# SCH_New-Project_2024-06-23.net
KiCad netlist of a schematic drawn in EasyEDA
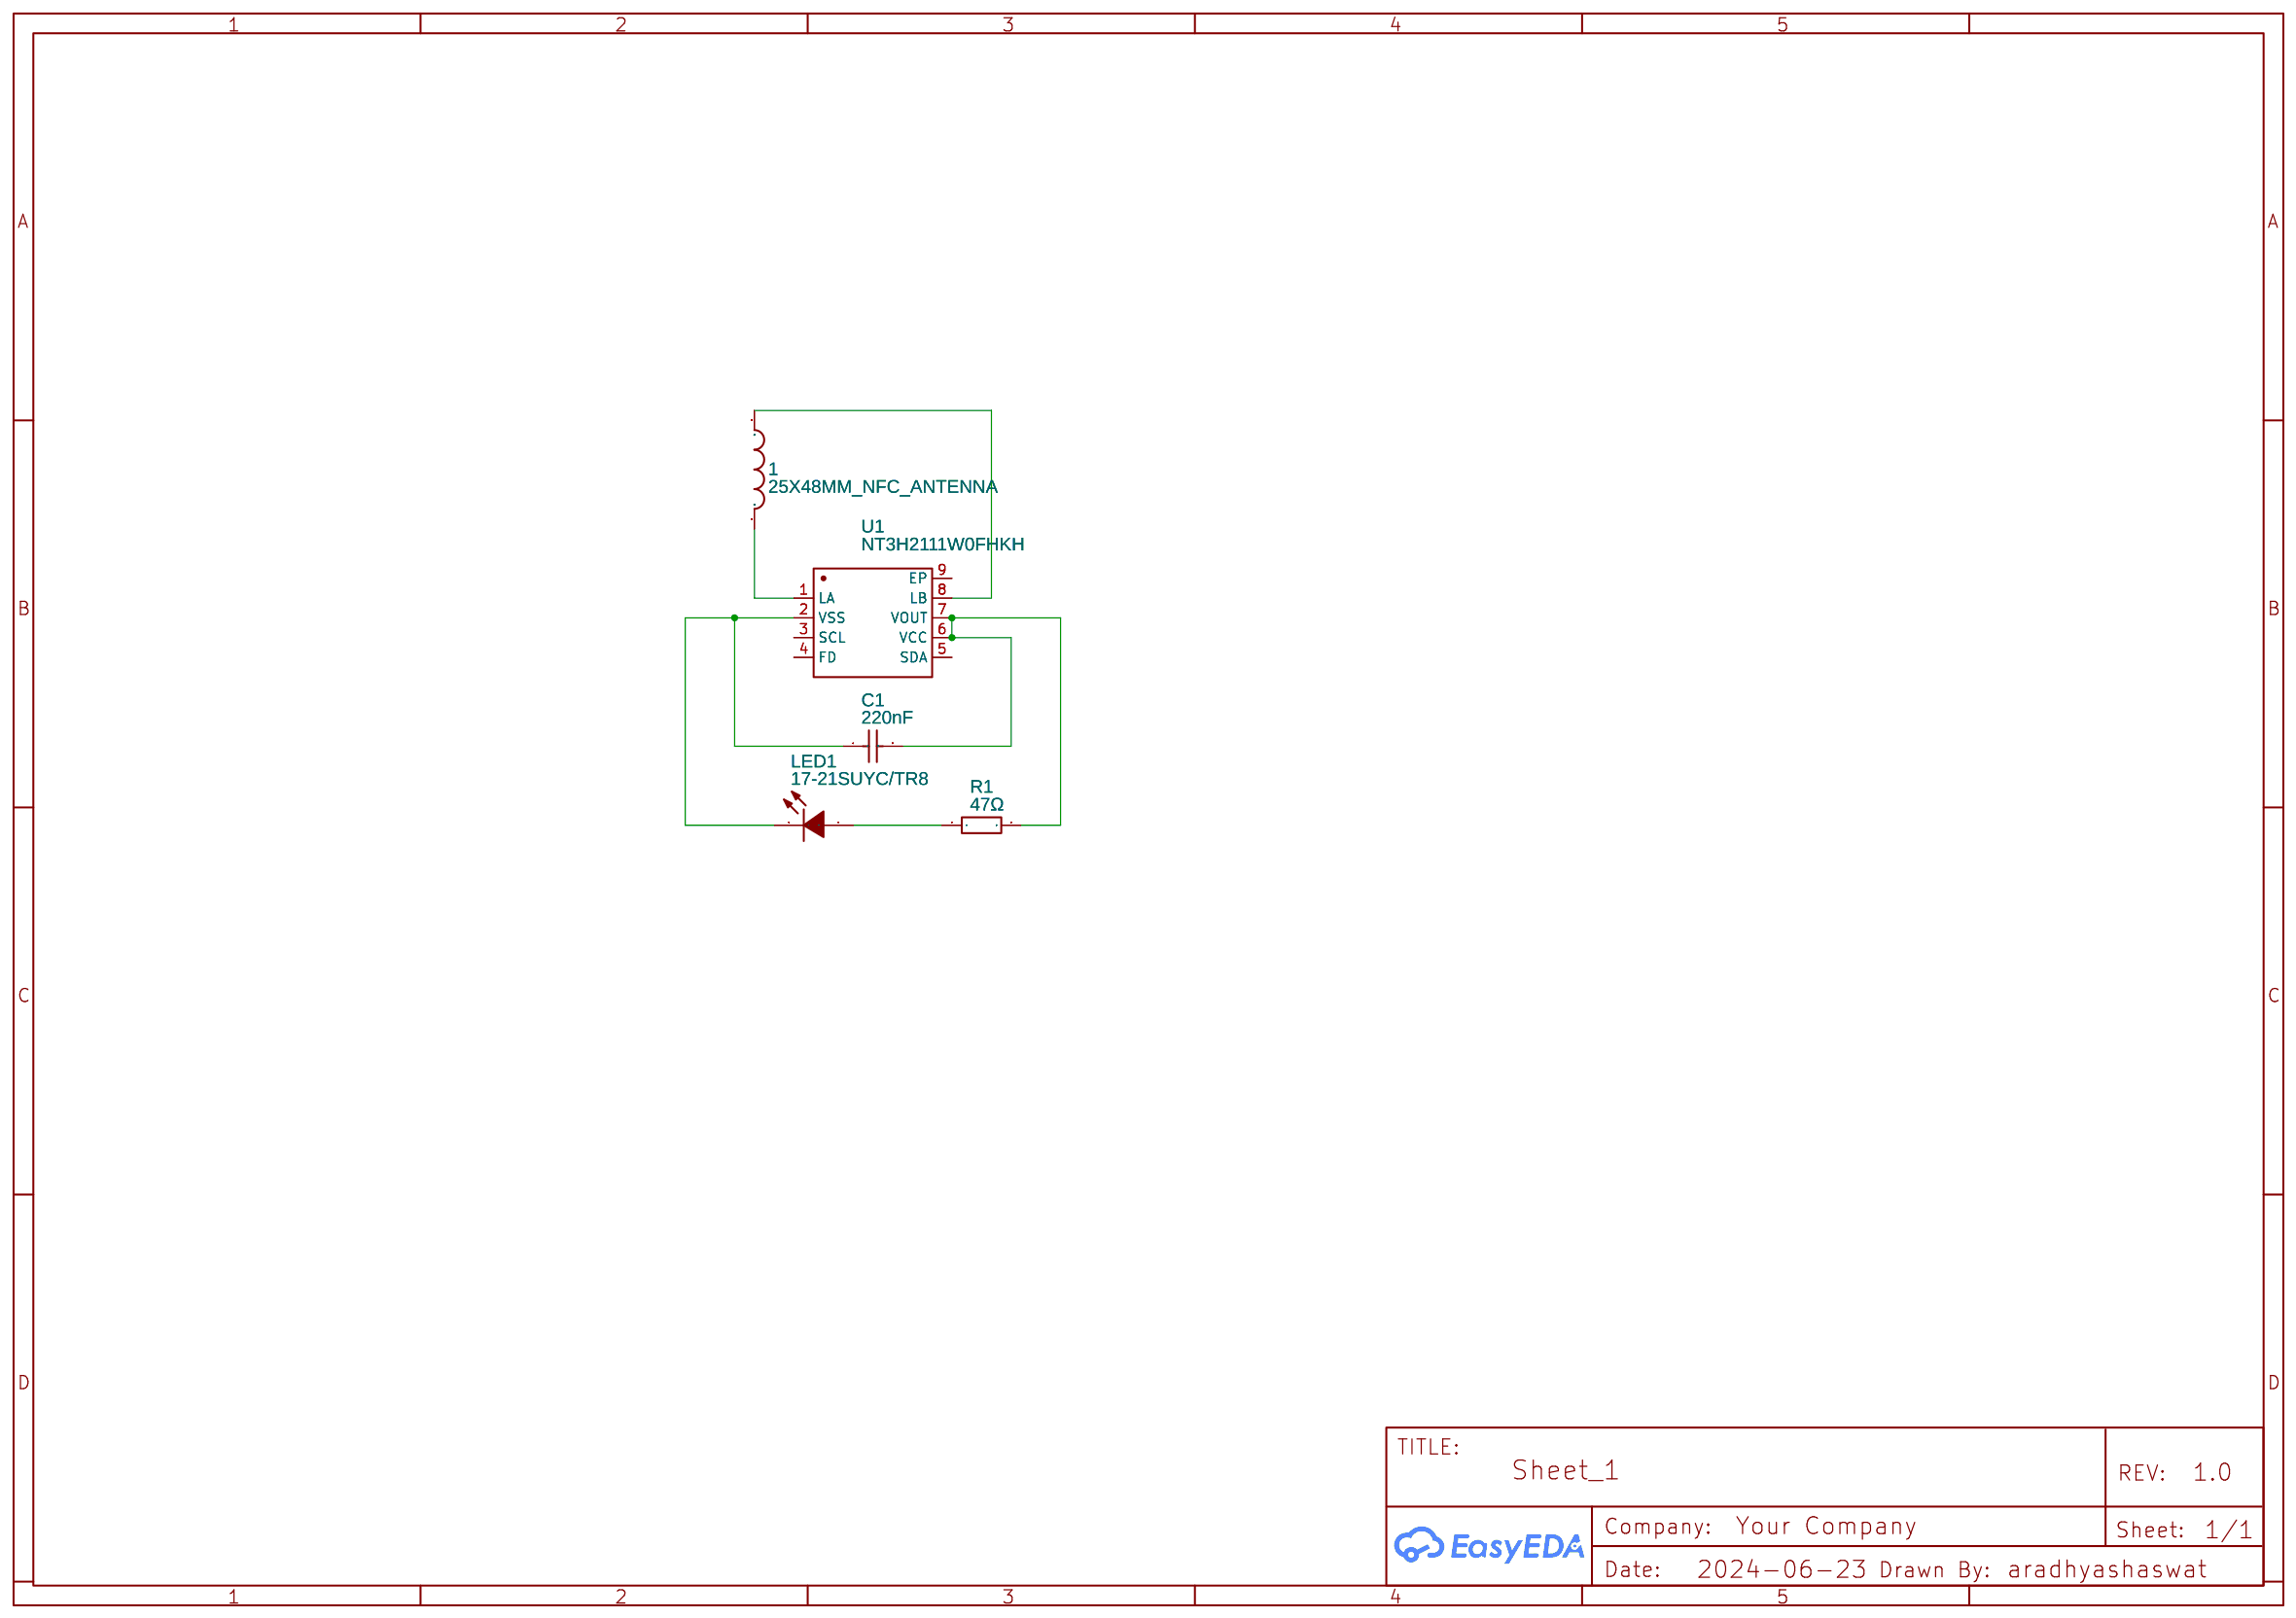
[diagram p0: schematic sheet]

(export (version "E")
  (design (tool "Eeschema 10.0.6"))
  (components
    (comp (ref "1") (value "25X48MM_NFC_ANTENNA") (libsource (lib "") (part "25X48MM_NFC_ANTENNA")))
    (comp (ref "C1")
      (value "220nF")
      (fields
        (field (name "Manufacturer Part") "CL10B224KA8NNNC")
        (field (name "Manufacturer") "SAMSUNG(三星)")
      )
      (libsource (lib "") (part "CL10B224KA8NNNC"))
    )
    (comp (ref "LED1")
      (value "17-21SUYC/TR8")
      (fields (field (name "Manufacturer Part") "KT-0805黄灯") (field (name "Manufacturer") "KENTO"))
      (libsource (lib "") (part "17-21SUYC/TR8"))
    )
    (comp (ref "R1")
      (value "47Ω")
      (fields
        (field (name "Manufacturer Part") "0603WAF470JT5E")
        (field (name "Manufacturer") "UNI-ROYAL(厚声)")
      )
      (libsource (lib "") (part "0603WAF470JT5E"))
    )
    (comp (ref "U1")
      (value "NT3H2111W0FHKH")
      (fields (field (name "Manufacturer") "NXP(恩智浦)"))
      (libsource (lib "") (part "NT3H2111W0FHKH"))
    )
  )
  (nets
    (net (code "1") (name "Net-(LED1-+)") (class "Default")
      (node (ref "LED1") (pin "1") (pinfunction "+_1") (pintype "unspecified"))
      (node (ref "R1") (pin "1") (pinfunction "1_1") (pintype "input"))
    )
    (net (code "2") (name "Net-(LED1--)") (class "Default")
      (node (ref "C1") (pin "1") (pinfunction "1_1") (pintype "input"))
      (node (ref "LED1") (pin "2") (pinfunction "-_2") (pintype "unspecified"))
      (node (ref "U1") (pin "2") (pinfunction "VSS_2") (pintype "unspecified"))
    )
    (net (code "3") (name "Net-(U1-LA)") (class "Default")
      (node (ref "1") (pin "P$2") (pinfunction "P$2_P$2") (pintype "bidirectional"))
      (node (ref "U1") (pin "1") (pinfunction "LA_1") (pintype "unspecified"))
    )
    (net (code "4") (name "Net-(U1-LB)") (class "Default")
      (node (ref "1") (pin "P$1") (pinfunction "P$1_P$1") (pintype "bidirectional"))
      (node (ref "U1") (pin "8") (pinfunction "LB_8") (pintype "unspecified"))
    )
    (net (code "5") (name "Net-(U1-VCC)") (class "Default")
      (node (ref "C1") (pin "2") (pinfunction "2_2") (pintype "input"))
      (node (ref "R1") (pin "2") (pinfunction "2_2") (pintype "input"))
      (node (ref "U1") (pin "6") (pinfunction "VCC_6") (pintype "unspecified"))
      (node (ref "U1") (pin "7") (pinfunction "VOUT_7") (pintype "unspecified"))
    )
    (net (code "6") (name "unconnected-(U1-EP-Pad9)") (class "Default")
      (node (ref "U1") (pin "9") (pinfunction "EP_9") (pintype "unspecified"))
    )
    (net (code "7") (name "unconnected-(U1-FD-Pad4)") (class "Default")
      (node (ref "U1") (pin "4") (pinfunction "FD_4") (pintype "unspecified"))
    )
    (net (code "8") (name "unconnected-(U1-SCL-Pad3)") (class "Default")
      (node (ref "U1") (pin "3") (pinfunction "SCL_3") (pintype "unspecified"))
    )
    (net (code "9") (name "unconnected-(U1-SDA-Pad5)") (class "Default")
      (node (ref "U1") (pin "5") (pinfunction "SDA_5") (pintype "unspecified"))
    )
  )
)
